# KHKT25.net
KiCad netlist of a schematic drawn in Altium Designer
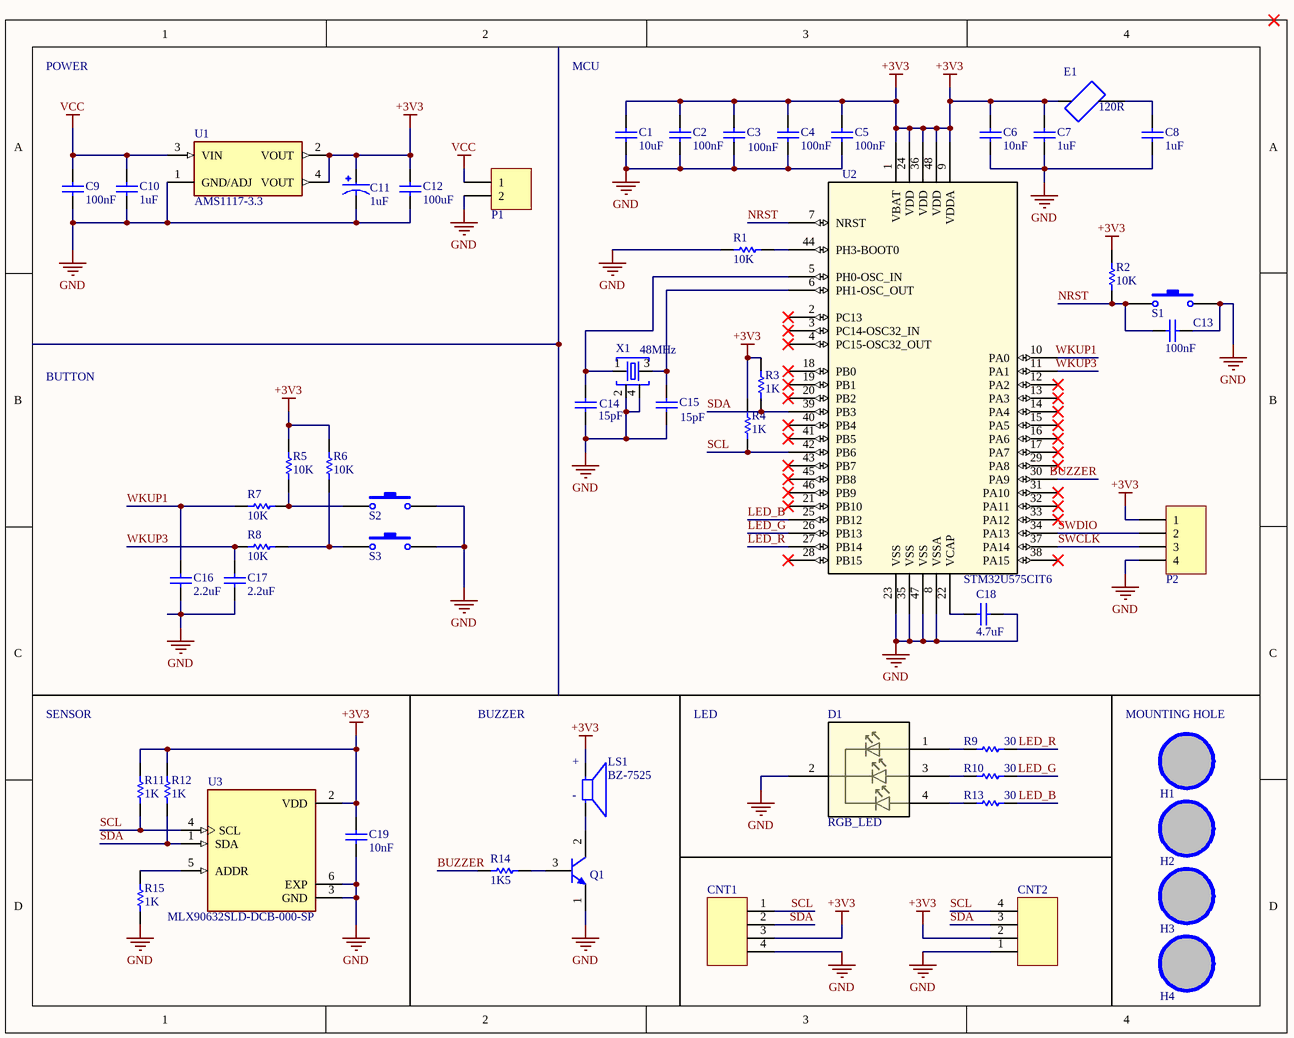
[diagram p0: KHKT25.SchDoc]

(export (version "E")
  (design (tool "Eeschema 10.0.6"))
  (components
    (comp (ref "C1")
      (value "10uF")
      (footprint "CAP-SM-0603")
      (description "Capacitor")
      (fields (field (name "Comment") "Cap Non-Pol SMD"))
      (libsource (lib "PIF_Library") (part "Cap Non-Pol SMD"))
    )
    (comp (ref "C2")
      (value "100nF")
      (footprint "CAP-SM-0603")
      (description "Capacitor")
      (fields (field (name "Comment") "Cap Non-Pol SMD"))
      (libsource (lib "PIF_Library") (part "Cap Non-Pol SMD"))
    )
    (comp (ref "C3")
      (value "100nF")
      (footprint "CAP-SM-0603")
      (description "Capacitor")
      (fields (field (name "Comment") "Cap Non-Pol SMD"))
      (libsource (lib "PIF_Library") (part "Cap Non-Pol SMD"))
    )
    (comp (ref "C4")
      (value "100nF")
      (footprint "CAP-SM-0603")
      (description "Capacitor")
      (fields (field (name "Comment") "Cap Non-Pol SMD"))
      (libsource (lib "PIF_Library") (part "Cap Non-Pol SMD"))
    )
    (comp (ref "C5")
      (value "100nF")
      (footprint "CAP-SM-0603")
      (description "Capacitor")
      (fields (field (name "Comment") "Cap Non-Pol SMD"))
      (libsource (lib "PIF_Library") (part "Cap Non-Pol SMD"))
    )
    (comp (ref "C6")
      (value "10nF")
      (footprint "CAP-SM-0603")
      (description "Capacitor")
      (fields (field (name "Comment") "Cap Non-Pol SMD"))
      (libsource (lib "PIF_Library") (part "Cap Non-Pol SMD"))
    )
    (comp (ref "C7")
      (value "1uF")
      (footprint "CAP-SM-0603")
      (description "Capacitor")
      (fields (field (name "Comment") "Cap Non-Pol SMD"))
      (libsource (lib "PIF_Library") (part "Cap Non-Pol SMD"))
    )
    (comp (ref "C8")
      (value "1uF")
      (footprint "CAP-SM-0603")
      (description "Capacitor")
      (fields (field (name "Comment") "Cap Non-Pol SMD"))
      (libsource (lib "PIF_Library") (part "Cap Non-Pol SMD"))
    )
    (comp (ref "C9")
      (value "100nF")
      (footprint "CAP-SM-0603")
      (description "Capacitor")
      (fields (field (name "Comment") "Cap Non-Pol SMD"))
      (libsource (lib "PIF_Library") (part "Cap Non-Pol SMD"))
    )
    (comp (ref "C10")
      (value "1uF")
      (footprint "CAP-SM-0603")
      (description "Capacitor")
      (fields (field (name "Comment") "Cap Non-Pol SMD"))
      (libsource (lib "PIF_Library") (part "Cap Non-Pol SMD"))
    )
    (comp (ref "C11")
      (value "1uF")
      (footprint "CAP_TAN_3216")
      (description "3216")
      (fields (field (name "MF") "KEMET") (field (name "MP") "T491A475K025AT"))
      (libsource (lib "IntLib") (part "Cap_Tantalum"))
    )
    (comp (ref "C12")
      (value "100uF")
      (footprint "CAP-SM-0603")
      (description "Capacitor")
      (fields (field (name "Comment") "Cap Non-Pol SMD"))
      (libsource (lib "PIF_Library") (part "Cap Non-Pol SMD"))
    )
    (comp (ref "C13")
      (value "100nF")
      (footprint "CAP-SM-0603")
      (description "Capacitor")
      (fields (field (name "Comment") "Cap Non-Pol SMD"))
      (libsource (lib "PIF_Library") (part "Cap Non-Pol SMD"))
    )
    (comp (ref "C14")
      (value "15pF")
      (footprint "CAP-SM-0603")
      (description "Capacitor")
      (fields (field (name "Comment") "Cap Non-Pol SMD"))
      (libsource (lib "PIF_Library") (part "Cap Non-Pol SMD"))
    )
    (comp (ref "C15")
      (value "15pF")
      (footprint "CAP-SM-0603")
      (description "Capacitor")
      (fields (field (name "Comment") "Cap Non-Pol SMD"))
      (libsource (lib "PIF_Library") (part "Cap Non-Pol SMD"))
    )
    (comp (ref "C16")
      (value "2.2uF")
      (footprint "CAP-SM-0603")
      (description "Capacitor")
      (fields (field (name "Comment") "Cap Non-Pol SMD"))
      (libsource (lib "PIF_Library") (part "Cap Non-Pol SMD"))
    )
    (comp (ref "C17")
      (value "2.2uF")
      (footprint "CAP-SM-0603")
      (description "Capacitor")
      (fields (field (name "Comment") "Cap Non-Pol SMD"))
      (libsource (lib "PIF_Library") (part "Cap Non-Pol SMD"))
    )
    (comp (ref "C18")
      (value "4.7uF")
      (footprint "CAP-SM-0603")
      (description "Capacitor")
      (fields (field (name "Comment") "Cap Non-Pol SMD"))
      (libsource (lib "PIF_Library") (part "Cap Non-Pol SMD"))
    )
    (comp (ref "C19")
      (value "10nF")
      (footprint "CAP_0402")
      (description "Capacitor")
      (fields (field (name "Comment") "Cap Non-Pol SMD"))
      (libsource (lib "PIF_Library") (part "Cap Non-Pol SMD"))
    )
    (comp (ref "CNT1") (value "HF4X1") (footprint "FPC_FFC_4P") (libsource (lib "") (part "HF4X1_1")))
    (comp (ref "CNT2") (value "HF4X1") (footprint "FPC_FFC_4P") (libsource (lib "IntLib") (part "HF4X1")))
    (comp (ref "D1")
      (value "RGB_LED")
      (footprint "RGB_LED")
      (description "Description")
      (fields
        (field (name "MANUFACTURER_PART_NUMBER") "L-154A4SURKQBDZGW")
        (field (name "COPYRIGHT") "Copyright (C) 2025 Ultra Librarian. All rights reserved.")
      )
      (libsource (lib "IntLib") (part "RGB_LED"))
    )
    (comp (ref "E1")
      (value "120R")
      (footprint "FB_MI0805K400R-10")
      (fields (field (name "MF") "Laird-Signal Integrity Products") (field (name "MP") "MI0805K400R-10"))
      (libsource (lib "IntLib") (part "MI0805K400R-10"))
    )
    (comp (ref "H1")
      (value "Hole")
      (footprint "LO KHOAN 3MM")
      (description "Hole 3mm")
      (libsource (lib "PIF_Library") (part "Hole"))
    )
    (comp (ref "H2")
      (value "Hole")
      (footprint "LO KHOAN 3MM")
      (description "Hole 3mm")
      (libsource (lib "PIF_Library") (part "Hole"))
    )
    (comp (ref "H3")
      (value "Hole")
      (footprint "LO KHOAN 3MM")
      (description "Hole 3mm")
      (libsource (lib "PIF_Library") (part "Hole"))
    )
    (comp (ref "H4")
      (value "Hole")
      (footprint "LO KHOAN 3MM")
      (description "Hole 3mm")
      (libsource (lib "PIF_Library") (part "Hole"))
    )
    (comp (ref "LS1")
      (value "BZ-7525")
      (footprint "XDCCMT-7525")
      (description "7.5 mm, 3.6 Vo-p, 80 dB, Surface Mount (SMT), Magnetic Audio Transducer Buzzer")
      (fields (field (name "MF") "Same Sky") (field (name "MP") "CMT-7525-80-SMT-TR"))
      (libsource (lib "IntLib") (part "BZ-7525"))
    )
    (comp (ref "P1")
      (value "Header 2")
      (footprint "DOMINO_2P")
      (description "Header, 2-Pin")
      (fields (field (name "PUBLISHER") "Altium Limited"))
      (libsource (lib "PIF_Library") (part "Header 2"))
    )
    (comp (ref "P2")
      (value "Header 4H")
      (footprint "JP4")
      (description "Header, 4-Pin, Right Angle")
      (fields (field (name "PUBLISHER") "Altium Limited"))
      (libsource (lib "PIF_Library") (part "Header 4H"))
    )
    (comp (ref "Q1")
      (value "C1815")
      (footprint "SOT23B")
      (description "NPN Bipolar Transistor")
      (libsource (lib "PIF_Library") (part "C1815"))
    )
    (comp (ref "R1")
      (value "10K")
      (footprint "RES-SM-0603")
      (description "Resistor")
      (fields (field (name "Comment") "RESISTOR SMD"))
      (libsource (lib "PIF_Library") (part "RESISTOR SMD"))
    )
    (comp (ref "R2")
      (value "10K")
      (footprint "RES-SM-0603")
      (description "Resistor")
      (fields (field (name "Comment") "RESISTOR SMD"))
      (libsource (lib "PIF_Library") (part "RESISTOR SMD"))
    )
    (comp (ref "R3")
      (value "1K")
      (footprint "RES-SM-0603")
      (description "Resistor")
      (fields (field (name "Comment") "RESISTOR SMD"))
      (libsource (lib "PIF_Library") (part "RESISTOR SMD"))
    )
    (comp (ref "R4")
      (value "1K")
      (footprint "RES-SM-0603")
      (description "Resistor")
      (fields (field (name "Comment") "RESISTOR SMD"))
      (libsource (lib "PIF_Library") (part "RESISTOR SMD"))
    )
    (comp (ref "R5")
      (value "10K")
      (footprint "RES-SM-0603")
      (description "Resistor")
      (fields (field (name "Comment") "RESISTOR SMD"))
      (libsource (lib "PIF_Library") (part "RESISTOR SMD"))
    )
    (comp (ref "R6")
      (value "10K")
      (footprint "RES-SM-0603")
      (description "Resistor")
      (fields (field (name "Comment") "RESISTOR SMD"))
      (libsource (lib "PIF_Library") (part "RESISTOR SMD"))
    )
    (comp (ref "R7")
      (value "10K")
      (footprint "RES-SM-0603")
      (description "Resistor")
      (fields (field (name "Comment") "RESISTOR SMD"))
      (libsource (lib "PIF_Library") (part "RESISTOR SMD"))
    )
    (comp (ref "R8")
      (value "10K")
      (footprint "RES-SM-0603")
      (description "Resistor")
      (fields (field (name "Comment") "RESISTOR SMD"))
      (libsource (lib "PIF_Library") (part "RESISTOR SMD"))
    )
    (comp (ref "R9")
      (value "30")
      (footprint "RES-SM-0603")
      (description "Resistor")
      (fields (field (name "Comment") "RESISTOR SMD"))
      (libsource (lib "PIF_Library") (part "RESISTOR SMD"))
    )
    (comp (ref "R10")
      (value "30")
      (footprint "RES-SM-0603")
      (description "Resistor")
      (fields (field (name "Comment") "RESISTOR SMD"))
      (libsource (lib "PIF_Library") (part "RESISTOR SMD"))
    )
    (comp (ref "R11")
      (value "1K")
      (footprint "RES_0402")
      (description "Resistor")
      (fields (field (name "Comment") "RESISTOR SMD"))
      (libsource (lib "PIF_Library") (part "RESISTOR SMD"))
    )
    (comp (ref "R12")
      (value "1K")
      (footprint "RES_0402")
      (description "Resistor")
      (fields (field (name "Comment") "RESISTOR SMD"))
      (libsource (lib "PIF_Library") (part "RESISTOR SMD"))
    )
    (comp (ref "R13")
      (value "30")
      (footprint "RES-SM-0603")
      (description "Resistor")
      (fields (field (name "Comment") "RESISTOR SMD"))
      (libsource (lib "PIF_Library") (part "RESISTOR SMD"))
    )
    (comp (ref "R14")
      (value "1K5")
      (footprint "RES-SM-0603")
      (description "Resistor")
      (fields (field (name "Comment") "RESISTOR SMD"))
      (libsource (lib "PIF_Library") (part "RESISTOR SMD"))
    )
    (comp (ref "R15")
      (value "1K")
      (footprint "RES_0402")
      (description "Resistor")
      (fields (field (name "Comment") "RESISTOR SMD"))
      (libsource (lib "PIF_Library") (part "RESISTOR SMD"))
    )
    (comp (ref "S1")
      (value "Tact SW - 2Pin")
      (footprint "SW_SMD")
      (description "Switch button 2 pin")
      (libsource (lib "PIF_Library") (part "Tact SW - 2Pin"))
    )
    (comp (ref "S2")
      (value "Tact SW - 2Pin")
      (footprint "SW_SMD")
      (description "Switch button 2 pin")
      (libsource (lib "PIF_Library") (part "Tact SW - 2Pin"))
    )
    (comp (ref "S3")
      (value "Tact SW - 2Pin")
      (footprint "SW_SMD")
      (description "Switch button 2 pin")
      (libsource (lib "PIF_Library") (part "Tact SW - 2Pin"))
    )
    (comp (ref "U1")
      (value "AMS1117-3.3")
      (footprint "SOT223-4N")
      (description "Sot223/Pkg 1-Amp 3.3-Volt Low Drop Out Voltage Regulatator")
      (fields (field (name "MF") "Advanced Monolithic Systems"))
      (libsource (lib "IntLib") (part "AMS1117-3.3"))
    )
    (comp (ref "U2")
      (value "STM32U575CIT6")
      (footprint "LQFP48-7x7mm_STM")
      (description "Ultra-low-power with FPU Arm Cortex-M33 MCU with TrustZone, 160 MHz with 2 Mbytes of Flash memory")
      (fields (field (name "COPYRIGHT") "Copyright (C) 2025 Ultra Librarian. All rights reserved."))
      (libsource (lib "IntLib") (part "STM32U575CIT6"))
    )
    (comp (ref "U3")
      (value "MLX90632SLD-DCB-000-SP")
      (footprint "MLX90632")
      (fields (field (name "MP") "MLX90632SLD-BCB-000-SP"))
      (libsource (lib "IntLib") (part "MLX90632SLD-BCB-000-SP"))
    )
    (comp (ref "X1")
      (value "48MHz")
      (footprint "TSX-3225")
      (description "Crystal")
      (fields (field (name "MF") "EPSON") (field (name "MP") "TSX-3225"))
      (libsource (lib "IntLib") (part "TSX-3225"))
    )
  )
  (nets
    (net (code "1") (name "+3V3") (class "Default")
      (node (ref "C1") (pin "2") (pinfunction "2_2") (pintype "passive"))
      (node (ref "C11") (pin "1") (pinfunction "1_1") (pintype "passive"))
      (node (ref "C12") (pin "2") (pinfunction "2_2") (pintype "passive"))
      (node (ref "C19") (pin "2") (pinfunction "2_2") (pintype "passive"))
      (node (ref "C2") (pin "2") (pinfunction "2_2") (pintype "passive"))
      (node (ref "C3") (pin "2") (pinfunction "2_2") (pintype "passive"))
      (node (ref "C4") (pin "2") (pinfunction "2_2") (pintype "passive"))
      (node (ref "C5") (pin "2") (pinfunction "2_2") (pintype "passive"))
      (node (ref "C6") (pin "2") (pinfunction "2_2") (pintype "passive"))
      (node (ref "C7") (pin "2") (pinfunction "2_2") (pintype "passive"))
      (node (ref "CNT1") (pin "3") (pintype "passive"))
      (node (ref "CNT2") (pin "2") (pintype "passive"))
      (node (ref "E1") (pin "1") (pinfunction "1_1") (pintype "passive"))
      (node (ref "LS1") (pin "P") (pinfunction "P_P") (pintype "passive"))
      (node (ref "P2") (pin "1") (pinfunction "1_1") (pintype "passive"))
      (node (ref "R11") (pin "1") (pinfunction "1_1") (pintype "passive"))
      (node (ref "R12") (pin "1") (pinfunction "1_1") (pintype "passive"))
      (node (ref "R2") (pin "1") (pinfunction "1_1") (pintype "passive"))
      (node (ref "R3") (pin "1") (pinfunction "1_1") (pintype "passive"))
      (node (ref "R4") (pin "1") (pinfunction "1_1") (pintype "passive"))
      (node (ref "R5") (pin "1") (pinfunction "1_1") (pintype "passive"))
      (node (ref "R6") (pin "1") (pinfunction "1_1") (pintype "passive"))
      (node (ref "U1") (pin "2") (pinfunction "VOUT_2") (pintype "output"))
      (node (ref "U1") (pin "4") (pinfunction "VOUT_4") (pintype "output"))
      (node (ref "U2") (pin "1") (pinfunction "VBAT_1") (pintype "power_in"))
      (node (ref "U2") (pin "24") (pinfunction "VDD_24") (pintype "power_in"))
      (node (ref "U2") (pin "36") (pinfunction "VDD_36") (pintype "power_in"))
      (node (ref "U2") (pin "48") (pinfunction "VDD_48") (pintype "power_in"))
      (node (ref "U2") (pin "9") (pinfunction "VDDA_9") (pintype "power_in"))
      (node (ref "U3") (pin "2") (pinfunction "VDD_2") (pintype "power_in"))
    )
    (net (code "2") (name "/BUZZER") (class "Default")
      (node (ref "R14") (pin "1") (pinfunction "1_1") (pintype "passive"))
      (node (ref "U2") (pin "30") (pinfunction "PA9_30") (pintype "bidirectional"))
    )
    (net (code "3") (name "/LED_B") (class "Default")
      (node (ref "R13") (pin "1") (pinfunction "1_1") (pintype "passive"))
      (node (ref "U2") (pin "25") (pinfunction "PB12_25") (pintype "bidirectional"))
    )
    (net (code "4") (name "/LED_G") (class "Default")
      (node (ref "R10") (pin "1") (pinfunction "1_1") (pintype "passive"))
      (node (ref "U2") (pin "26") (pinfunction "PB13_26") (pintype "bidirectional"))
    )
    (net (code "5") (name "/LED_R") (class "Default")
      (node (ref "R9") (pin "1") (pinfunction "1_1") (pintype "passive"))
      (node (ref "U2") (pin "27") (pinfunction "PB14_27") (pintype "bidirectional"))
    )
    (net (code "6") (name "/NRST") (class "Default")
      (node (ref "C13") (pin "1") (pinfunction "1_1") (pintype "passive"))
      (node (ref "R2") (pin "2") (pinfunction "2_2") (pintype "passive"))
      (node (ref "S1") (pin "1") (pinfunction "1_1") (pintype "passive"))
      (node (ref "U2") (pin "7") (pinfunction "NRST_7") (pintype "bidirectional"))
    )
    (net (code "7") (name "/SCL") (class "Default")
      (node (ref "CNT1") (pin "1") (pintype "passive"))
      (node (ref "CNT2") (pin "4") (pintype "passive"))
      (node (ref "R11") (pin "2") (pinfunction "2_2") (pintype "passive"))
      (node (ref "R4") (pin "2") (pinfunction "2_2") (pintype "passive"))
      (node (ref "U2") (pin "42") (pinfunction "PB6_42") (pintype "bidirectional"))
      (node (ref "U3") (pin "4") (pinfunction "SCL_4") (pintype "input"))
    )
    (net (code "8") (name "/SDA") (class "Default")
      (node (ref "CNT1") (pin "2") (pintype "passive"))
      (node (ref "CNT2") (pin "3") (pintype "passive"))
      (node (ref "R12") (pin "2") (pinfunction "2_2") (pintype "passive"))
      (node (ref "R3") (pin "2") (pinfunction "2_2") (pintype "passive"))
      (node (ref "U2") (pin "39") (pinfunction "PB3_39") (pintype "bidirectional"))
      (node (ref "U3") (pin "1") (pinfunction "SDA_1") (pintype "input"))
    )
    (net (code "9") (name "/SWCLK") (class "Default")
      (node (ref "P2") (pin "3") (pinfunction "3_3") (pintype "passive"))
      (node (ref "U2") (pin "37") (pinfunction "PA14_37") (pintype "bidirectional"))
    )
    (net (code "10") (name "/SWDIO") (class "Default")
      (node (ref "P2") (pin "2") (pinfunction "2_2") (pintype "passive"))
      (node (ref "U2") (pin "34") (pinfunction "PA13_34") (pintype "bidirectional"))
    )
    (net (code "11") (name "/WKUP1") (class "Default")
      (node (ref "C16") (pin "2") (pinfunction "2_2") (pintype "passive"))
      (node (ref "R7") (pin "1") (pinfunction "1_1") (pintype "passive"))
      (node (ref "U2") (pin "10") (pinfunction "PA0_10") (pintype "bidirectional"))
    )
    (net (code "12") (name "/WKUP3") (class "Default")
      (node (ref "C17") (pin "2") (pinfunction "2_2") (pintype "passive"))
      (node (ref "R8") (pin "1") (pinfunction "1_1") (pintype "passive"))
      (node (ref "U2") (pin "11") (pinfunction "PA1_11") (pintype "bidirectional"))
    )
    (net (code "13") (name "GND") (class "Default")
      (node (ref "C1") (pin "1") (pinfunction "1_1") (pintype "passive"))
      (node (ref "C10") (pin "1") (pinfunction "1_1") (pintype "passive"))
      (node (ref "C11") (pin "2") (pinfunction "2_2") (pintype "passive"))
      (node (ref "C12") (pin "1") (pinfunction "1_1") (pintype "passive"))
      (node (ref "C13") (pin "2") (pinfunction "2_2") (pintype "passive"))
      (node (ref "C14") (pin "1") (pinfunction "1_1") (pintype "passive"))
      (node (ref "C15") (pin "1") (pinfunction "1_1") (pintype "passive"))
      (node (ref "C16") (pin "1") (pinfunction "1_1") (pintype "passive"))
      (node (ref "C17") (pin "1") (pinfunction "1_1") (pintype "passive"))
      (node (ref "C18") (pin "1") (pinfunction "1_1") (pintype "passive"))
      (node (ref "C19") (pin "1") (pinfunction "1_1") (pintype "passive"))
      (node (ref "C2") (pin "1") (pinfunction "1_1") (pintype "passive"))
      (node (ref "C3") (pin "1") (pinfunction "1_1") (pintype "passive"))
      (node (ref "C4") (pin "1") (pinfunction "1_1") (pintype "passive"))
      (node (ref "C5") (pin "1") (pinfunction "1_1") (pintype "passive"))
      (node (ref "C6") (pin "1") (pinfunction "1_1") (pintype "passive"))
      (node (ref "C7") (pin "1") (pinfunction "1_1") (pintype "passive"))
      (node (ref "C8") (pin "1") (pinfunction "1_1") (pintype "passive"))
      (node (ref "C9") (pin "1") (pinfunction "1_1") (pintype "passive"))
      (node (ref "CNT1") (pin "4") (pintype "passive"))
      (node (ref "CNT2") (pin "1") (pintype "passive"))
      (node (ref "D1") (pin "2") (pinfunction "2_2") (pintype "passive"))
      (node (ref "P1") (pin "2") (pinfunction "2_2") (pintype "passive"))
      (node (ref "P2") (pin "4") (pinfunction "4_4") (pintype "passive"))
      (node (ref "Q1") (pin "1") (pinfunction "E_1") (pintype "passive"))
      (node (ref "R1") (pin "2") (pinfunction "2_2") (pintype "passive"))
      (node (ref "R15") (pin "2") (pinfunction "2_2") (pintype "passive"))
      (node (ref "S1") (pin "2") (pinfunction "2_2") (pintype "passive"))
      (node (ref "S2") (pin "2") (pinfunction "2_2") (pintype "passive"))
      (node (ref "S3") (pin "2") (pinfunction "2_2") (pintype "passive"))
      (node (ref "U1") (pin "1") (pinfunction "GND/ADJ_1") (pintype "power_in"))
      (node (ref "U2") (pin "23") (pinfunction "VSS_23") (pintype "power_in"))
      (node (ref "U2") (pin "35") (pinfunction "VSS_35") (pintype "power_in"))
      (node (ref "U2") (pin "47") (pinfunction "VSS_47") (pintype "power_in"))
      (node (ref "U2") (pin "8") (pinfunction "VSSA_8") (pintype "power_in"))
      (node (ref "U3") (pin "3") (pinfunction "GND_3") (pintype "power_in"))
      (node (ref "U3") (pin "6") (pinfunction "EXP_6") (pintype "power_in"))
      (node (ref "X1") (pin "2") (pinfunction "2_2") (pintype "passive"))
      (node (ref "X1") (pin "4") (pinfunction "4_4") (pintype "passive"))
    )
    (net (code "14") (name "Net-(C8-Pad2)") (class "Default")
      (node (ref "C8") (pin "2") (pinfunction "2_2") (pintype "passive"))
      (node (ref "E1") (pin "2") (pinfunction "2_2") (pintype "passive"))
    )
    (net (code "15") (name "Net-(D1-Pad1)") (class "Default")
      (node (ref "D1") (pin "1") (pinfunction "1_1") (pintype "passive"))
      (node (ref "R9") (pin "2") (pinfunction "2_2") (pintype "passive"))
    )
    (net (code "16") (name "Net-(D1-Pad3)") (class "Default")
      (node (ref "D1") (pin "3") (pinfunction "3_3") (pintype "passive"))
      (node (ref "R10") (pin "2") (pinfunction "2_2") (pintype "passive"))
    )
    (net (code "17") (name "Net-(D1-Pad4)") (class "Default")
      (node (ref "D1") (pin "4") (pinfunction "4_4") (pintype "passive"))
      (node (ref "R13") (pin "2") (pinfunction "2_2") (pintype "passive"))
    )
    (net (code "18") (name "Net-(Q1-B)") (class "Default")
      (node (ref "Q1") (pin "3") (pinfunction "B_3") (pintype "passive"))
      (node (ref "R14") (pin "2") (pinfunction "2_2") (pintype "passive"))
    )
    (net (code "19") (name "Net-(Q1-C)") (class "Default")
      (node (ref "LS1") (pin "N") (pinfunction "N_N") (pintype "passive"))
      (node (ref "Q1") (pin "2") (pinfunction "C_2") (pintype "passive"))
    )
    (net (code "20") (name "Net-(R5-Pad2)") (class "Default")
      (node (ref "R5") (pin "2") (pinfunction "2_2") (pintype "passive"))
      (node (ref "R7") (pin "2") (pinfunction "2_2") (pintype "passive"))
      (node (ref "S2") (pin "1") (pinfunction "1_1") (pintype "passive"))
    )
    (net (code "21") (name "Net-(R6-Pad2)") (class "Default")
      (node (ref "R6") (pin "2") (pinfunction "2_2") (pintype "passive"))
      (node (ref "R8") (pin "2") (pinfunction "2_2") (pintype "passive"))
      (node (ref "S3") (pin "1") (pinfunction "1_1") (pintype "passive"))
    )
    (net (code "22") (name "Net-(U2-PH0-OSC_IN)") (class "Default")
      (node (ref "C14") (pin "2") (pinfunction "2_2") (pintype "passive"))
      (node (ref "U2") (pin "5") (pinfunction "PH0-OSC_IN_5") (pintype "bidirectional"))
      (node (ref "X1") (pin "1") (pinfunction "1_1") (pintype "passive"))
    )
    (net (code "23") (name "Net-(U2-PH1-OSC_OUT)") (class "Default")
      (node (ref "C15") (pin "2") (pinfunction "2_2") (pintype "passive"))
      (node (ref "U2") (pin "6") (pinfunction "PH1-OSC_OUT_6") (pintype "bidirectional"))
      (node (ref "X1") (pin "3") (pinfunction "3_3") (pintype "passive"))
    )
    (net (code "24") (name "Net-(U2-PH3-BOOT0)") (class "Default")
      (node (ref "R1") (pin "1") (pinfunction "1_1") (pintype "passive"))
      (node (ref "U2") (pin "44") (pinfunction "PH3-BOOT0_44") (pintype "bidirectional"))
    )
    (net (code "25") (name "Net-(U2-VCAP)") (class "Default")
      (node (ref "C18") (pin "2") (pinfunction "2_2") (pintype "passive"))
      (node (ref "U2") (pin "22") (pinfunction "VCAP_22") (pintype "power_in"))
    )
    (net (code "26") (name "Net-(U3-ADDR)") (class "Default")
      (node (ref "R15") (pin "1") (pinfunction "1_1") (pintype "passive"))
      (node (ref "U3") (pin "5") (pinfunction "ADDR_5") (pintype "input"))
    )
    (net (code "27") (name "VCC") (class "Default")
      (node (ref "C10") (pin "2") (pinfunction "2_2") (pintype "passive"))
      (node (ref "C9") (pin "2") (pinfunction "2_2") (pintype "passive"))
      (node (ref "P1") (pin "1") (pinfunction "1_1") (pintype "passive"))
      (node (ref "U1") (pin "3") (pinfunction "VIN_3") (pintype "input"))
    )
    (net (code "28") (name "unconnected-(H1-Pad1)") (class "Default")
      (node (ref "H1") (pin "1") (pinfunction "1_1") (pintype "passive"))
    )
    (net (code "29") (name "unconnected-(H2-Pad1)") (class "Default")
      (node (ref "H2") (pin "1") (pinfunction "1_1") (pintype "passive"))
    )
    (net (code "30") (name "unconnected-(H3-Pad1)") (class "Default")
      (node (ref "H3") (pin "1") (pinfunction "1_1") (pintype "passive"))
    )
    (net (code "31") (name "unconnected-(H4-Pad1)") (class "Default")
      (node (ref "H4") (pin "1") (pinfunction "1_1") (pintype "passive"))
    )
    (net (code "32") (name "unconnected-(U2-PA2-Pad12)") (class "Default")
      (node (ref "U2") (pin "12") (pinfunction "PA2_12") (pintype "bidirectional+no_connect"))
    )
    (net (code "33") (name "unconnected-(U2-PA3-Pad13)") (class "Default")
      (node (ref "U2") (pin "13") (pinfunction "PA3_13") (pintype "bidirectional+no_connect"))
    )
    (net (code "34") (name "unconnected-(U2-PA4-Pad14)") (class "Default")
      (node (ref "U2") (pin "14") (pinfunction "PA4_14") (pintype "bidirectional+no_connect"))
    )
    (net (code "35") (name "unconnected-(U2-PA5-Pad15)") (class "Default")
      (node (ref "U2") (pin "15") (pinfunction "PA5_15") (pintype "bidirectional+no_connect"))
    )
    (net (code "36") (name "unconnected-(U2-PA6-Pad16)") (class "Default")
      (node (ref "U2") (pin "16") (pinfunction "PA6_16") (pintype "bidirectional+no_connect"))
    )
    (net (code "37") (name "unconnected-(U2-PA7-Pad17)") (class "Default")
      (node (ref "U2") (pin "17") (pinfunction "PA7_17") (pintype "bidirectional+no_connect"))
    )
    (net (code "38") (name "unconnected-(U2-PA8-Pad29)") (class "Default")
      (node (ref "U2") (pin "29") (pinfunction "PA8_29") (pintype "bidirectional+no_connect"))
    )
    (net (code "39") (name "unconnected-(U2-PA10-Pad31)") (class "Default")
      (node (ref "U2") (pin "31") (pinfunction "PA10_31") (pintype "bidirectional+no_connect"))
    )
    (net (code "40") (name "unconnected-(U2-PA11-Pad32)") (class "Default")
      (node (ref "U2") (pin "32") (pinfunction "PA11_32") (pintype "bidirectional+no_connect"))
    )
    (net (code "41") (name "unconnected-(U2-PA12-Pad33)") (class "Default")
      (node (ref "U2") (pin "33") (pinfunction "PA12_33") (pintype "bidirectional+no_connect"))
    )
    (net (code "42") (name "unconnected-(U2-PA15-Pad38)") (class "Default")
      (node (ref "U2") (pin "38") (pinfunction "PA15_38") (pintype "bidirectional+no_connect"))
    )
    (net (code "43") (name "unconnected-(U2-PB0-Pad18)") (class "Default")
      (node (ref "U2") (pin "18") (pinfunction "PB0_18") (pintype "bidirectional+no_connect"))
    )
    (net (code "44") (name "unconnected-(U2-PB1-Pad19)") (class "Default")
      (node (ref "U2") (pin "19") (pinfunction "PB1_19") (pintype "bidirectional+no_connect"))
    )
    (net (code "45") (name "unconnected-(U2-PB2-Pad20)") (class "Default")
      (node (ref "U2") (pin "20") (pinfunction "PB2_20") (pintype "bidirectional+no_connect"))
    )
    (net (code "46") (name "unconnected-(U2-PB4-Pad40)") (class "Default")
      (node (ref "U2") (pin "40") (pinfunction "PB4_40") (pintype "bidirectional+no_connect"))
    )
    (net (code "47") (name "unconnected-(U2-PB5-Pad41)") (class "Default")
      (node (ref "U2") (pin "41") (pinfunction "PB5_41") (pintype "bidirectional+no_connect"))
    )
    (net (code "48") (name "unconnected-(U2-PB7-Pad43)") (class "Default")
      (node (ref "U2") (pin "43") (pinfunction "PB7_43") (pintype "bidirectional+no_connect"))
    )
    (net (code "49") (name "unconnected-(U2-PB8-Pad45)") (class "Default")
      (node (ref "U2") (pin "45") (pinfunction "PB8_45") (pintype "bidirectional+no_connect"))
    )
    (net (code "50") (name "unconnected-(U2-PB9-Pad46)") (class "Default")
      (node (ref "U2") (pin "46") (pinfunction "PB9_46") (pintype "bidirectional+no_connect"))
    )
    (net (code "51") (name "unconnected-(U2-PB10-Pad21)") (class "Default")
      (node (ref "U2") (pin "21") (pinfunction "PB10_21") (pintype "bidirectional+no_connect"))
    )
    (net (code "52") (name "unconnected-(U2-PB15-Pad28)") (class "Default")
      (node (ref "U2") (pin "28") (pinfunction "PB15_28") (pintype "bidirectional+no_connect"))
    )
    (net (code "53") (name "unconnected-(U2-PC13-Pad2)") (class "Default")
      (node (ref "U2") (pin "2") (pinfunction "PC13_2") (pintype "bidirectional+no_connect"))
    )
    (net (code "54") (name "unconnected-(U2-PC14-OSC32_IN-Pad3)") (class "Default")
      (node (ref "U2") (pin "3") (pinfunction "PC14-OSC32_IN_3") (pintype "bidirectional+no_connect"))
    )
    (net (code "55") (name "unconnected-(U2-PC15-OSC32_OUT-Pad4)") (class "Default")
      (node (ref "U2") (pin "4") (pinfunction "PC15-OSC32_OUT_4") (pintype "bidirectional+no_connect"))
    )
  )
)
